# Battery_chargers.net
KiCad netlist of a schematic drawn in Altium Designer
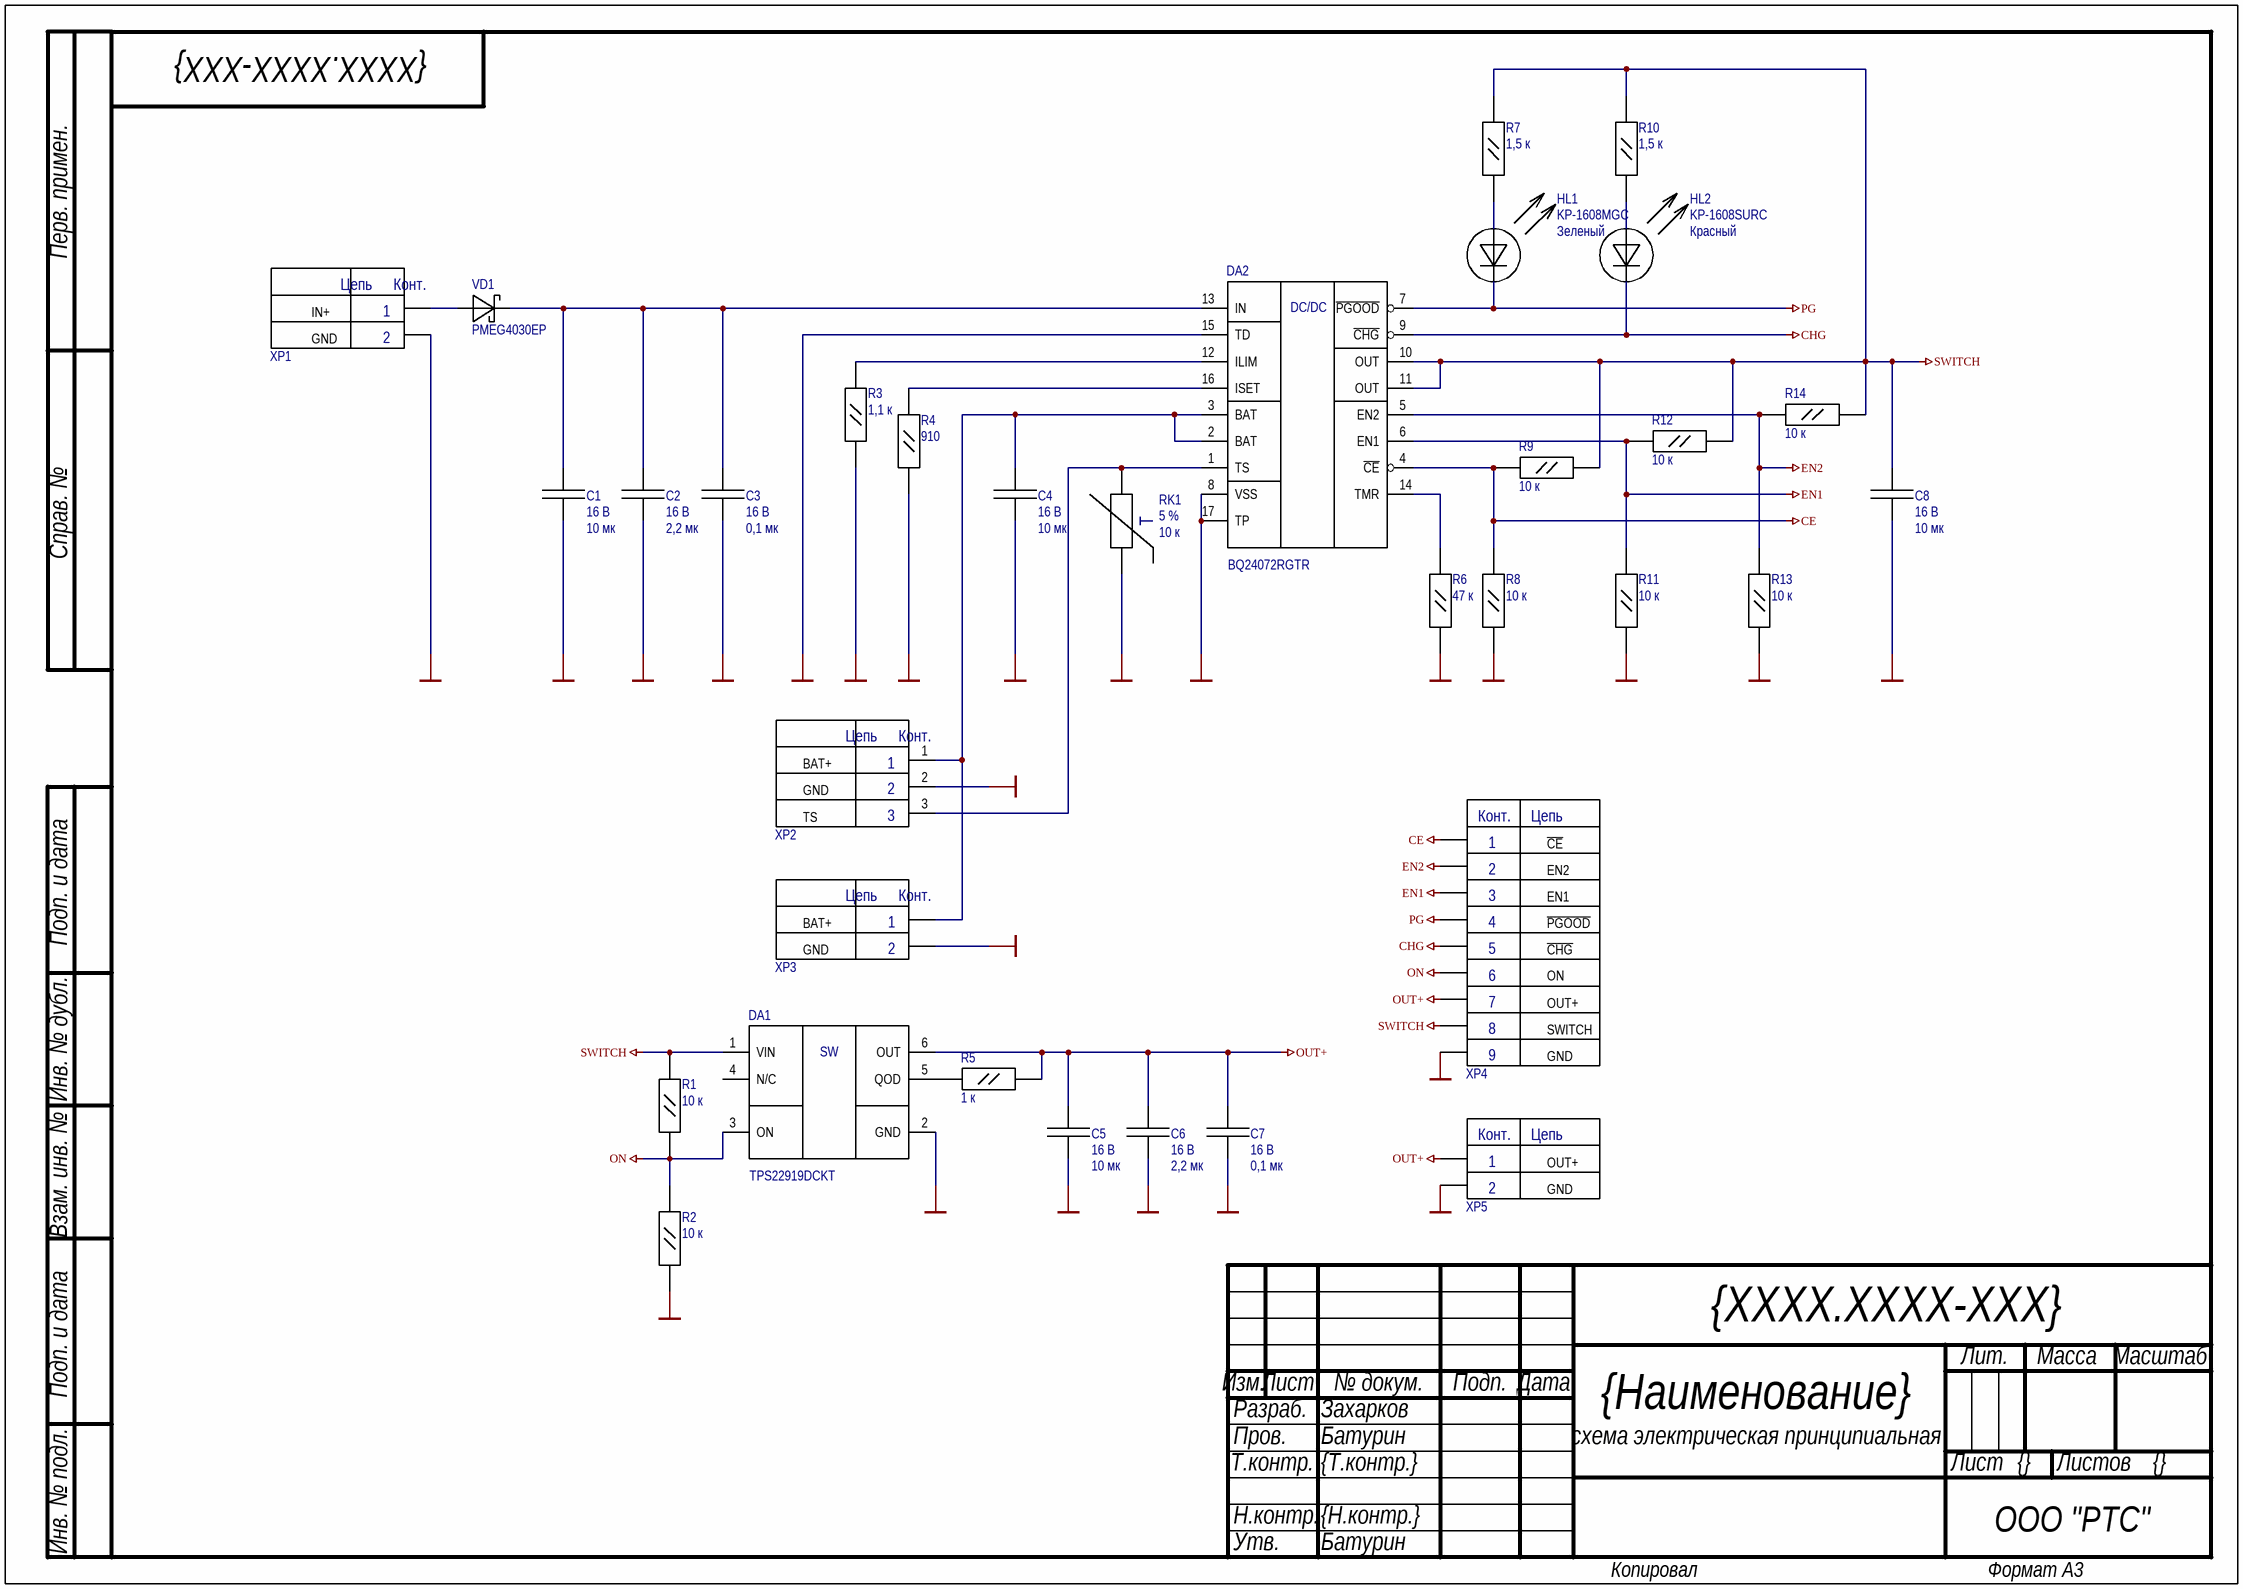
[diagram p0: Battery chargers.SchDoc]

(export (version "E")
  (design (tool "Eeschema 10.0.6"))
  (components
    (comp (ref "C1")
      (value "10 мк")
      (footprint "C_0603_Manual_mount")
      (description "Chip Monolithic Ceramic Capacitor")
      (fields
        (field (name "TOLERANCE") "20 %")
        (field (name "MANUFACTURER") "Murata Manufacturing")
        (field (name "RATED VOLTAGE") "16 В")
      )
      (libsource (lib "passive") (part "Capacitor"))
    )
    (comp (ref "C2")
      (value "2,2 мк")
      (footprint "C_0603_Manual_mount")
      (description "Chip Monolithic Ceramic Capacitor")
      (fields
        (field (name "TOLERANCE") "10 %")
        (field (name "MANUFACTURER") "Murata Manufacturing")
        (field (name "RATED VOLTAGE") "16 В")
      )
      (libsource (lib "passive") (part "Capacitor"))
    )
    (comp (ref "C3")
      (value "0,1 мк")
      (footprint "C_0603_Manual_mount")
      (description "Surface-mount Ceramic Multilayer Capacitor")
      (fields
        (field (name "TOLERANCE") "10 %")
        (field (name "MANUFACTURER") "YAGEO")
        (field (name "RATED VOLTAGE") "16 В")
      )
      (libsource (lib "passive") (part "Capacitor"))
    )
    (comp (ref "C4")
      (value "10 мк")
      (footprint "C_0603_Manual_mount")
      (description "Chip Monolithic Ceramic Capacitor")
      (fields
        (field (name "TOLERANCE") "20 %")
        (field (name "MANUFACTURER") "Murata Manufacturing")
        (field (name "RATED VOLTAGE") "16 В")
      )
      (libsource (lib "passive") (part "Capacitor"))
    )
    (comp (ref "C5")
      (value "10 мк")
      (footprint "C_0603_Manual_mount")
      (description "Chip Monolithic Ceramic Capacitor")
      (fields
        (field (name "TOLERANCE") "20 %")
        (field (name "MANUFACTURER") "Murata Manufacturing")
        (field (name "RATED VOLTAGE") "16 В")
      )
      (libsource (lib "passive") (part "Capacitor"))
    )
    (comp (ref "C6")
      (value "2,2 мк")
      (footprint "C_0603_Manual_mount")
      (description "Chip Monolithic Ceramic Capacitor")
      (fields
        (field (name "TOLERANCE") "10 %")
        (field (name "MANUFACTURER") "Murata Manufacturing")
        (field (name "RATED VOLTAGE") "16 В")
      )
      (libsource (lib "passive") (part "Capacitor"))
    )
    (comp (ref "C7")
      (value "0,1 мк")
      (footprint "C_0603_Manual_mount")
      (description "Surface-mount Ceramic Multilayer Capacitor")
      (fields
        (field (name "TOLERANCE") "10 %")
        (field (name "MANUFACTURER") "YAGEO")
        (field (name "RATED VOLTAGE") "16 В")
      )
      (libsource (lib "passive") (part "Capacitor"))
    )
    (comp (ref "C8")
      (value "10 мк")
      (footprint "C_0603_Manual_mount")
      (description "Chip Monolithic Ceramic Capacitor")
      (fields
        (field (name "TOLERANCE") "20 %")
        (field (name "MANUFACTURER") "Murata Manufacturing")
        (field (name "RATED VOLTAGE") "16 В")
      )
      (libsource (lib "passive") (part "Capacitor"))
    )
    (comp (ref "DA1")
      (value "TPS22919DCKT")
      (footprint "SC70")
      (description "5.5 V, 1.5 A, 90-mΩ Self-Protected Load Switch with Controlled Rise Time")
      (fields (field (name "MANUFACTURER") "Texas Instruments"))
      (libsource (lib "Integrated_BQ24072RGTR") (part "TPS22919DCKT"))
    )
    (comp (ref "DA2")
      (value "BQ24072RGTR")
      (footprint "VQFN-16")
      (description "Standalone 1-Cell 1.5-A Linear Battery Chargers with Power Path")
      (fields (field (name "MANUFACTURER") "Texas Instruments"))
      (libsource (lib "Integrated_BQ24072RGTR") (part "BQ24072RGTR"))
    )
    (comp (ref "HL1")
      (value "KP-1608MGC")
      (footprint "LED_0603_Green_Manual_mount")
      (description "SMD LED")
      (fields (field (name "MANUFACTURER") "Kingbright") (field (name "COLOR") "Зеленый"))
      (libsource (lib "altium-lib") (part "KP-1608MGC"))
    )
    (comp (ref "HL2")
      (value "KP-1608SURC")
      (footprint "LED_0603_Red_Manual_mount")
      (description "SMD LED")
      (fields (field (name "MANUFACTURER") "Kingbright") (field (name "COLOR") "Красный"))
      (libsource (lib "altium-lib") (part "KP-1608SURC"))
    )
    (comp (ref "R1")
      (value "10 к")
      (footprint "R_0603_Manual_mount")
      (description "General Purpose Chip Resistor")
      (fields (field (name "TOLERANCE") "5 %") (field (name "MANUFACTURER") "YAGEO"))
      (libsource (lib "passive") (part "Resistor_0.125W"))
    )
    (comp (ref "R2")
      (value "10 к")
      (footprint "R_0603_Manual_mount")
      (description "General Purpose Chip Resistor")
      (fields (field (name "TOLERANCE") "5 %") (field (name "MANUFACTURER") "YAGEO"))
      (libsource (lib "passive") (part "Resistor_0.125W"))
    )
    (comp (ref "R3")
      (value "1,1 к")
      (footprint "R_0603_Manual_mount")
      (description "General Purpose Chip Resistor")
      (fields (field (name "TOLERANCE") "5 %") (field (name "MANUFACTURER") "YAGEO"))
      (libsource (lib "passive") (part "Resistor_0.125W"))
    )
    (comp (ref "R4")
      (value "910")
      (footprint "R_0603_Manual_mount")
      (description "General Purpose Chip Resistor")
      (fields (field (name "TOLERANCE") "5 %") (field (name "MANUFACTURER") "YAGEO"))
      (libsource (lib "passive") (part "Resistor_0.125W"))
    )
    (comp (ref "R5")
      (value "1 к")
      (footprint "R_0603_Manual_mount")
      (description "General Purpose Chip Resistor")
      (fields (field (name "TOLERANCE") "5 %") (field (name "MANUFACTURER") "YAGEO"))
      (libsource (lib "passive") (part "Resistor_0.125W"))
    )
    (comp (ref "R6")
      (value "47 к")
      (footprint "R_0603_Manual_mount")
      (description "General Purpose Chip Resistor")
      (fields (field (name "TOLERANCE") "5 %") (field (name "MANUFACTURER") "YAGEO"))
      (libsource (lib "passive") (part "Resistor_0.125W"))
    )
    (comp (ref "R7")
      (value "1,5 к")
      (footprint "R_0603_Manual_mount")
      (description "General Purpose Chip Resistor")
      (fields (field (name "TOLERANCE") "5 %") (field (name "MANUFACTURER") "YAGEO"))
      (libsource (lib "passive") (part "Resistor_0.125W"))
    )
    (comp (ref "R8")
      (value "10 к")
      (footprint "R_0603_Manual_mount")
      (description "General Purpose Chip Resistor")
      (fields (field (name "TOLERANCE") "5 %") (field (name "MANUFACTURER") "YAGEO"))
      (libsource (lib "passive") (part "Resistor_0.125W"))
    )
    (comp (ref "R9")
      (value "10 к")
      (footprint "R_0603_Manual_mount")
      (description "General Purpose Chip Resistor")
      (fields (field (name "TOLERANCE") "5 %") (field (name "MANUFACTURER") "YAGEO"))
      (libsource (lib "passive") (part "Resistor_0.125W"))
    )
    (comp (ref "R10")
      (value "1,5 к")
      (footprint "R_0603_Manual_mount")
      (description "General Purpose Chip Resistor")
      (fields (field (name "TOLERANCE") "5 %") (field (name "MANUFACTURER") "YAGEO"))
      (libsource (lib "passive") (part "Resistor_0.125W"))
    )
    (comp (ref "R11")
      (value "10 к")
      (footprint "R_0603_Manual_mount")
      (description "General Purpose Chip Resistor")
      (fields (field (name "TOLERANCE") "5 %") (field (name "MANUFACTURER") "YAGEO"))
      (libsource (lib "passive") (part "Resistor_0.125W"))
    )
    (comp (ref "R12")
      (value "10 к")
      (footprint "R_0603_Manual_mount")
      (description "General Purpose Chip Resistor")
      (fields (field (name "TOLERANCE") "5 %") (field (name "MANUFACTURER") "YAGEO"))
      (libsource (lib "passive") (part "Resistor_0.125W"))
    )
    (comp (ref "R13")
      (value "10 к")
      (footprint "R_0603_Manual_mount")
      (description "General Purpose Chip Resistor")
      (fields (field (name "TOLERANCE") "5 %") (field (name "MANUFACTURER") "YAGEO"))
      (libsource (lib "passive") (part "Resistor_0.125W"))
    )
    (comp (ref "R14")
      (value "10 к")
      (footprint "R_0603_Manual_mount")
      (description "General Purpose Chip Resistor")
      (fields (field (name "TOLERANCE") "5 %") (field (name "MANUFACTURER") "YAGEO"))
      (libsource (lib "passive") (part "Resistor_0.125W"))
    )
    (comp (ref "RK1")
      (value "10 к")
      (footprint "RK_0603_Manual_Mount")
      (description "NTC Thermistor")
      (fields
        (field (name "MANUFACTURER") "Vishay")
        (field (name "TOLERANCE") "5 %")
        (field (name "PART NUMBER") "NTHS0603N02N1002J")
      )
      (libsource (lib "passive") (part "Thermistor"))
    )
    (comp (ref "VD1")
      (value "PMEG4030EP")
      (footprint "SOD-128")
      (description "3 A low VF MEGA Schottky barrier rectifier")
      (fields (field (name "MANUFACTURER") "NXP"))
      (libsource (lib "altium-lib") (part "PMEG4030EP"))
    )
    (comp (ref "XP1")
      (value "DS1069-2MVW6X")
      (footprint "DS1069-2MVxxX")
      (description "2.5mm-step power connector")
      (fields (field (name "MANUFACTURER") "CONNFLY"))
      (libsource (lib "altium-lib") (part "DS1069-2MVW6X"))
    )
    (comp (ref "XP2")
      (value "DS1069-3MVW6X")
      (footprint "DS1069-3MVW6X")
      (description "2.5mm-step power connector")
      (fields (field (name "MANUFACTURER") "CONNFLY"))
      (libsource (lib "Integrated_BQ24072RGTR") (part "DS1069-3MVW6X"))
    )
    (comp (ref "XP3")
      (value "DS1069-2MVW6X")
      (footprint "DS1069-2MVxxX")
      (description "2.5mm-step power connector")
      (fields (field (name "MANUFACTURER") "CONNFLY"))
      (libsource (lib "altium-lib") (part "DS1069-2MVW6X"))
    )
    (comp (ref "XP4")
      (value "PLS-9")
      (footprint "PLS-9")
      (description "PLS connector")
      (fields (field (name "MANUFACTURER") "NONAME"))
      (libsource (lib "altium-lib") (part "PLS-9"))
    )
    (comp (ref "XP5")
      (value "DS1069-2MVW6X")
      (footprint "DS1069-2MVxxX")
      (description "2.5mm-step power connector")
      (fields (field (name "MANUFACTURER") "CONNFLY"))
      (libsource (lib "altium-lib") (part "DS1069-2MVW6X"))
    )
  )
  (nets
    (net (code "4") (name "CE") (class "Default")
      (node (ref "DA2") (pin "4") (pinfunction "~{CE}_4") (pintype "passive"))
      (node (ref "R8") (pin "2") (pinfunction "2_2") (pintype "passive"))
      (node (ref "R9") (pin "1") (pinfunction "1_1") (pintype "passive"))
      (node (ref "XP4") (pin "1") (pinfunction "1_1") (pintype "passive"))
    )
    (net (code "5") (name "CHG") (class "Default")
      (node (ref "DA2") (pin "9") (pinfunction "~{CHG}_9") (pintype "passive"))
      (node (ref "HL2") (pin "C") (pinfunction "C_C") (pintype "passive"))
      (node (ref "XP4") (pin "5") (pinfunction "5_5") (pintype "passive"))
    )
    (net (code "6") (name "EN1") (class "Default")
      (node (ref "DA2") (pin "6") (pinfunction "EN1_6") (pintype "passive"))
      (node (ref "R11") (pin "2") (pinfunction "2_2") (pintype "passive"))
      (node (ref "R12") (pin "1") (pinfunction "1_1") (pintype "passive"))
      (node (ref "XP4") (pin "3") (pinfunction "3_3") (pintype "passive"))
    )
    (net (code "7") (name "EN2") (class "Default")
      (node (ref "DA2") (pin "5") (pinfunction "EN2_5") (pintype "passive"))
      (node (ref "R13") (pin "2") (pinfunction "2_2") (pintype "passive"))
      (node (ref "R14") (pin "1") (pinfunction "1_1") (pintype "passive"))
      (node (ref "XP4") (pin "2") (pinfunction "2_2") (pintype "passive"))
    )
    (net (code "8") (name "GND") (class "Default")
      (node (ref "C1") (pin "2") (pinfunction "2_2") (pintype "passive"))
      (node (ref "C2") (pin "2") (pinfunction "2_2") (pintype "passive"))
      (node (ref "C3") (pin "2") (pinfunction "2_2") (pintype "passive"))
      (node (ref "C4") (pin "2") (pinfunction "2_2") (pintype "passive"))
      (node (ref "C5") (pin "2") (pinfunction "2_2") (pintype "passive"))
      (node (ref "C6") (pin "2") (pinfunction "2_2") (pintype "passive"))
      (node (ref "C7") (pin "2") (pinfunction "2_2") (pintype "passive"))
      (node (ref "C8") (pin "2") (pinfunction "2_2") (pintype "passive"))
      (node (ref "DA1") (pin "2") (pinfunction "GND_2") (pintype "passive"))
      (node (ref "DA2") (pin "15") (pinfunction "TD_15") (pintype "passive"))
      (node (ref "DA2") (pin "17") (pinfunction "TP_17") (pintype "passive"))
      (node (ref "DA2") (pin "8") (pinfunction "VSS_8") (pintype "passive"))
      (node (ref "R11") (pin "1") (pinfunction "1_1") (pintype "passive"))
      (node (ref "R13") (pin "1") (pinfunction "1_1") (pintype "passive"))
      (node (ref "R2") (pin "1") (pinfunction "1_1") (pintype "passive"))
      (node (ref "R3") (pin "1") (pinfunction "1_1") (pintype "passive"))
      (node (ref "R4") (pin "1") (pinfunction "1_1") (pintype "passive"))
      (node (ref "R6") (pin "1") (pinfunction "1_1") (pintype "passive"))
      (node (ref "R8") (pin "1") (pinfunction "1_1") (pintype "passive"))
      (node (ref "RK1") (pin "1") (pinfunction "1_1") (pintype "passive"))
      (node (ref "XP1") (pin "2") (pinfunction "2_2") (pintype "passive"))
      (node (ref "XP2") (pin "2") (pinfunction "2_2") (pintype "passive"))
      (node (ref "XP3") (pin "2") (pinfunction "2_2") (pintype "passive"))
      (node (ref "XP4") (pin "9") (pinfunction "9_9") (pintype "passive"))
      (node (ref "XP5") (pin "2") (pinfunction "2_2") (pintype "passive"))
    )
    (net (code "9") (name "Net-(C4-Pad1)") (class "Default")
      (node (ref "C4") (pin "1") (pinfunction "1_1") (pintype "passive"))
      (node (ref "DA2") (pin "2") (pinfunction "BAT_2") (pintype "passive"))
      (node (ref "DA2") (pin "3") (pinfunction "BAT_3") (pintype "passive"))
      (node (ref "XP2") (pin "1") (pinfunction "1_1") (pintype "passive"))
      (node (ref "XP3") (pin "1") (pinfunction "1_1") (pintype "passive"))
    )
    (net (code "10") (name "Net-(DA1-QOD)") (class "Default")
      (node (ref "DA1") (pin "5") (pinfunction "QOD_5") (pintype "passive"))
      (node (ref "R5") (pin "1") (pinfunction "1_1") (pintype "passive"))
    )
    (net (code "11") (name "Net-(DA2-ILIM)") (class "Default")
      (node (ref "DA2") (pin "12") (pinfunction "ILIM_12") (pintype "passive"))
      (node (ref "R3") (pin "2") (pinfunction "2_2") (pintype "passive"))
    )
    (net (code "12") (name "Net-(DA2-IN)") (class "Default")
      (node (ref "C1") (pin "1") (pinfunction "1_1") (pintype "passive"))
      (node (ref "C2") (pin "1") (pinfunction "1_1") (pintype "passive"))
      (node (ref "C3") (pin "1") (pinfunction "1_1") (pintype "passive"))
      (node (ref "DA2") (pin "13") (pinfunction "IN_13") (pintype "passive"))
      (node (ref "VD1") (pin "C") (pinfunction "C_C") (pintype "passive"))
    )
    (net (code "13") (name "Net-(DA2-ISET)") (class "Default")
      (node (ref "DA2") (pin "16") (pinfunction "ISET_16") (pintype "passive"))
      (node (ref "R4") (pin "2") (pinfunction "2_2") (pintype "passive"))
    )
    (net (code "14") (name "Net-(DA2-TMR)") (class "Default")
      (node (ref "DA2") (pin "14") (pinfunction "TMR_14") (pintype "passive"))
      (node (ref "R6") (pin "2") (pinfunction "2_2") (pintype "passive"))
    )
    (net (code "15") (name "Net-(DA2-TS)") (class "Default")
      (node (ref "DA2") (pin "1") (pinfunction "TS_1") (pintype "passive"))
      (node (ref "RK1") (pin "2") (pinfunction "2_2") (pintype "passive"))
      (node (ref "XP2") (pin "3") (pinfunction "3_3") (pintype "passive"))
    )
    (net (code "16") (name "Net-(HL1-PadA)") (class "Default")
      (node (ref "HL1") (pin "A") (pinfunction "A_A") (pintype "passive"))
      (node (ref "R7") (pin "1") (pinfunction "1_1") (pintype "passive"))
    )
    (net (code "17") (name "Net-(HL2-PadA)") (class "Default")
      (node (ref "HL2") (pin "A") (pinfunction "A_A") (pintype "passive"))
      (node (ref "R10") (pin "1") (pinfunction "1_1") (pintype "passive"))
    )
    (net (code "18") (name "Net-(VD1-PadA)") (class "Default")
      (node (ref "VD1") (pin "A") (pinfunction "A_A") (pintype "passive"))
      (node (ref "XP1") (pin "1") (pinfunction "1_1") (pintype "passive"))
    )
    (net (code "19") (name "ON") (class "Default")
      (node (ref "DA1") (pin "3") (pinfunction "ON_3") (pintype "passive"))
      (node (ref "R1") (pin "1") (pinfunction "1_1") (pintype "passive"))
      (node (ref "R2") (pin "2") (pinfunction "2_2") (pintype "passive"))
      (node (ref "XP4") (pin "6") (pinfunction "6_6") (pintype "passive"))
    )
    (net (code "20") (name "OUT+") (class "Default")
      (node (ref "C5") (pin "1") (pinfunction "1_1") (pintype "passive"))
      (node (ref "C6") (pin "1") (pinfunction "1_1") (pintype "passive"))
      (node (ref "C7") (pin "1") (pinfunction "1_1") (pintype "passive"))
      (node (ref "DA1") (pin "6") (pinfunction "OUT_6") (pintype "passive"))
      (node (ref "R5") (pin "2") (pinfunction "2_2") (pintype "passive"))
      (node (ref "XP4") (pin "7") (pinfunction "7_7") (pintype "passive"))
      (node (ref "XP5") (pin "1") (pinfunction "1_1") (pintype "passive"))
    )
    (net (code "21") (name "PG") (class "Default")
      (node (ref "DA2") (pin "7") (pinfunction "~{PGOOD}_7") (pintype "passive"))
      (node (ref "HL1") (pin "C") (pinfunction "C_C") (pintype "passive"))
      (node (ref "XP4") (pin "4") (pinfunction "4_4") (pintype "passive"))
    )
    (net (code "22") (name "SWITCH") (class "Default")
      (node (ref "C8") (pin "1") (pinfunction "1_1") (pintype "passive"))
      (node (ref "DA1") (pin "1") (pinfunction "VIN_1") (pintype "passive"))
      (node (ref "DA2") (pin "10") (pinfunction "OUT_10") (pintype "passive"))
      (node (ref "DA2") (pin "11") (pinfunction "OUT_11") (pintype "passive"))
      (node (ref "R1") (pin "2") (pinfunction "2_2") (pintype "passive"))
      (node (ref "R10") (pin "2") (pinfunction "2_2") (pintype "passive"))
      (node (ref "R12") (pin "2") (pinfunction "2_2") (pintype "passive"))
      (node (ref "R14") (pin "2") (pinfunction "2_2") (pintype "passive"))
      (node (ref "R7") (pin "2") (pinfunction "2_2") (pintype "passive"))
      (node (ref "R9") (pin "2") (pinfunction "2_2") (pintype "passive"))
      (node (ref "XP4") (pin "8") (pinfunction "8_8") (pintype "passive"))
    )
    (net (code "23") (name "unconnected-(DA1-N{slash}C-Pad4)") (class "Default")
      (node (ref "DA1") (pin "4") (pinfunction "N/C_4") (pintype "passive"))
    )
  )
)
